# ncp1117.net
KiCad netlist of a schematic drawn in EAGLE
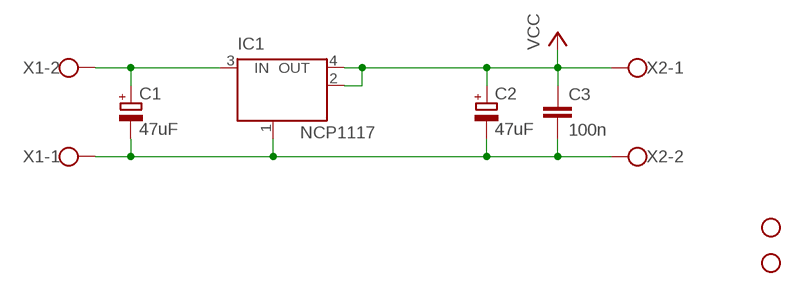
[diagram p0: schematic, sheet 1]

(export (version "E")
  (design (tool "Eeschema 10.0.6"))
  (components
    (comp (ref "C1")
      (value "47uF")
      (footprint "eagle-import:E2,5-5")
      (libsource (lib "eagle-import") (part "CPOL-EUE2.5-5"))
    )
    (comp (ref "C2")
      (value "47uF")
      (footprint "eagle-import:E2,5-5")
      (libsource (lib "eagle-import") (part "CPOL-EUE2.5-5"))
    )
    (comp (ref "C3")
      (value "100n")
      (footprint "eagle-import:C1206K")
      (libsource (lib "eagle-import") (part "C-EUC1206K"))
    )
    (comp (ref "IC1")
      (value "NCP1117")
      (footprint "eagle-import:SOT223")
      (libsource (lib "eagle-import") (part "MC33269ST-3.3T3"))
    )
    (comp (ref "STANDOFF1")
      (value "STAND-OFF")
      (footprint "eagle-import:STAND-OFF")
      (libsource (lib "eagle-import") (part "STAND-OFF"))
    )
    (comp (ref "STANDOFF2")
      (value "STAND-OFF")
      (footprint "eagle-import:STAND-OFF")
      (libsource (lib "eagle-import") (part "STAND-OFF"))
    )
    (comp (ref "X1")
      (value "W237-102")
      (footprint "eagle-import:W237-102")
      (fields (field (name "MPN") "237-102"))
      (libsource (lib "eagle-import") (part "W237-102"))
    )
    (comp (ref "X2")
      (value "W237-102")
      (footprint "eagle-import:W237-102")
      (fields (field (name "MPN") "237-102"))
      (libsource (lib "eagle-import") (part "W237-102"))
    )
  )
  (nets
    (net (code "1") (name "Net-(IC1-GND{slash}ADJ)") (class "Default")
      (node (ref "C1") (pin "-") (pinfunction "-_-") (pintype "passive"))
      (node (ref "C2") (pin "-") (pinfunction "-_-") (pintype "passive"))
      (node (ref "C3") (pin "2") (pinfunction "2_2") (pintype "passive"))
      (node (ref "IC1") (pin "1") (pinfunction "GND/ADJ_1") (pintype "input"))
      (node (ref "X1") (pin "1") (pinfunction "KL_1") (pintype "passive"))
      (node (ref "X2") (pin "2") (pinfunction "KL_2") (pintype "passive"))
    )
    (net (code "2") (name "Net-(IC1-IN)") (class "Default")
      (node (ref "C1") (pin "+") (pinfunction "+_+") (pintype "passive"))
      (node (ref "IC1") (pin "3") (pinfunction "IN_3") (pintype "input"))
      (node (ref "X1") (pin "2") (pinfunction "KL_2") (pintype "passive"))
    )
    (net (code "3") (name "VCC") (class "Default")
      (node (ref "C2") (pin "+") (pinfunction "+_+") (pintype "passive"))
      (node (ref "C3") (pin "1") (pinfunction "1_1") (pintype "passive"))
      (node (ref "IC1") (pin "2") (pinfunction "OUT_2") (pintype "passive"))
      (node (ref "IC1") (pin "4") (pinfunction "OUT_4") (pintype "passive"))
      (node (ref "X2") (pin "1") (pinfunction "KL_1") (pintype "passive"))
    )
  )
)
